# Timer555.net
KiCad netlist of a schematic drawn in Altium Designer
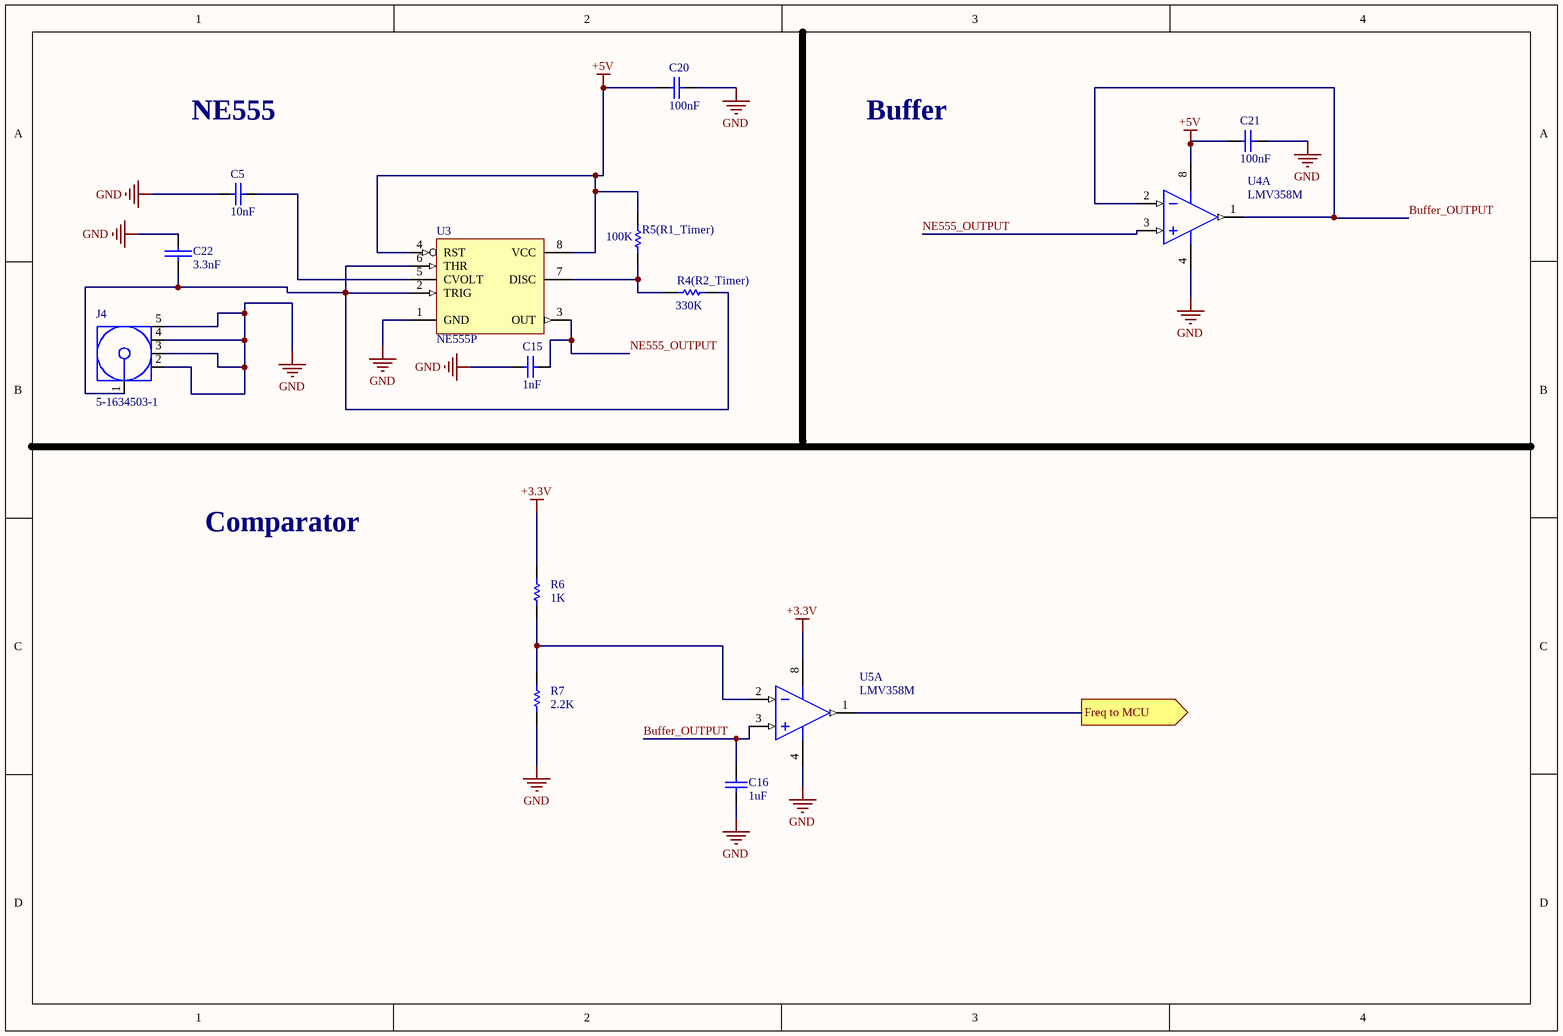
[diagram p0: Timer555.SchDoc]

(export (version "E")
  (design (tool "Eeschema 10.0.6"))
  (components
    (comp (ref "C5")
      (value "10nF")
      (footprint "CAPC2012N (0805)")
      (description "Bipolar Capacitor")
      (fields
        (field (name "VOLTAGE") "100V")
        (field (name "DESIGNER") "Eng. Saeid Jorablo")
        (field (name "PUBLISHER") "SJ Unlimited")
      )
      (libsource (lib "Passive Components") (part "CAP_Bipolar"))
    )
    (comp (ref "C15")
      (value "1nF")
      (footprint "CAPC3216M (1206)")
      (description "Bipolar Capacitor")
      (fields
        (field (name "VOLTAGE") "100V")
        (field (name "DESIGNER") "Eng. Saeid Jorablo")
        (field (name "PUBLISHER") "SJ Unlimited")
      )
      (libsource (lib "Passive Components") (part "CAP_Bipolar"))
    )
    (comp (ref "C16")
      (value "1uF")
      (footprint "CAPC3216M (1206)")
      (description "Bipolar Capacitor")
      (fields
        (field (name "VOLTAGE") "100V")
        (field (name "DESIGNER") "Eng. Saeid Jorablo")
        (field (name "PUBLISHER") "SJ Unlimited")
      )
      (libsource (lib "Passive Components") (part "CAP_Bipolar"))
    )
    (comp (ref "C20")
      (value "100nF")
      (footprint "CAPC2012N (0805)")
      (description "Bipolar Capacitor")
      (fields
        (field (name "VOLTAGE") "100V")
        (field (name "DESIGNER") "Eng. Saeid Jorablo")
        (field (name "PUBLISHER") "SJ Unlimited")
      )
      (libsource (lib "Passive Components") (part "CAP_Bipolar"))
    )
    (comp (ref "C21")
      (value "100nF")
      (footprint "CAPC2012N (0805)")
      (description "Bipolar Capacitor")
      (fields
        (field (name "VOLTAGE") "100V")
        (field (name "DESIGNER") "Eng. Saeid Jorablo")
        (field (name "PUBLISHER") "SJ Unlimited")
      )
      (libsource (lib "Passive Components") (part "CAP_Bipolar"))
    )
    (comp (ref "C22")
      (value "3.3nF")
      (footprint "Cap - 100nF")
      (description "Bipolar Capacitor")
      (fields (field (name "VOLTAGE") "100V") (field (name "DESIGNER") "Saeid Jorablo"))
      (libsource (lib "General 2") (part "Cap-Bipolar"))
    )
    (comp (ref "J4")
      (value "5-1634503-1")
      (footprint "TECO-5-1634503-1_V")
      (description "Female Header, Pitch 3.13 mm, Height 13.7 mm, Tail Length 4.5 mm, -55 to 85 degC, RoHS, Bulk")
      (fields (field (name "MANUFACTURER") "TE Connectivity"))
      (libsource (lib "Amir_Lib") (part "5-1634503-1"))
    )
    (comp (ref "R4(R2_Timer)")
      (value "330K")
      (footprint "Res-(1/2)")
      (description "Resistor")
      (fields
        (field (name "TOLERANCE") "5%")
        (field (name "POWER") "1/8 W")
        (field (name "DESIGNER") "Eng. Saeid Jorablo")
        (field (name "PUBLISHER") "SJ Unlimited")
      )
      (libsource (lib "Passive Components") (part "RES"))
    )
    (comp (ref "R5(R1_Timer)")
      (value "100K")
      (footprint "Res-(1/2)")
      (description "Resistor")
      (fields
        (field (name "TOLERANCE") "5%")
        (field (name "POWER") "1/8 W")
        (field (name "DESIGNER") "Eng. Saeid Jorablo")
        (field (name "PUBLISHER") "SJ Unlimited")
      )
      (libsource (lib "Passive Components") (part "RES"))
    )
    (comp (ref "R6")
      (value "1K")
      (footprint "RESC3216X60L (1206)")
      (description "Resistor")
      (fields
        (field (name "TOLERANCE") "5%")
        (field (name "POWER") "1/8 W")
        (field (name "DESIGNER") "Eng. Saeid Jorablo")
        (field (name "PUBLISHER") "SJ Unlimited")
      )
      (libsource (lib "Passive Components") (part "RES"))
    )
    (comp (ref "R7")
      (value "2.2K")
      (footprint "RESC3216X60L (1206)")
      (description "Resistor")
      (fields
        (field (name "TOLERANCE") "5%")
        (field (name "POWER") "1/8 W")
        (field (name "DESIGNER") "Eng. Saeid Jorablo")
        (field (name "PUBLISHER") "SJ Unlimited")
      )
      (libsource (lib "Passive Components") (part "RES"))
    )
    (comp (ref "U3")
      (value "NE555P")
      (footprint "P008")
      (description "Precision Timer")
      (fields (field (name "PUBLISHER") "Altium Limited"))
      (libsource (lib "TI Analog Timer Circuit") (part "NE555P"))
    )
    (comp (ref "U4")
      (value "LMV358M")
      (footprint "M08A_M")
      (description "General Purpose, Low Voltage, Rail-to-Rail Output Operational Amplifiers, 8-pin Narrow SOIC")
      (fields (field (name "MANUFACTURER") "National Semiconductor"))
      (libsource (lib "Xilinx") (part "LMV358M"))
    )
    (comp (ref "U5")
      (value "LMV358M")
      (footprint "M08A_M")
      (description "General Purpose, Low Voltage, Rail-to-Rail Output Operational Amplifiers, 8-pin Narrow SOIC")
      (fields (field (name "MANUFACTURER") "National Semiconductor"))
      (libsource (lib "Xilinx") (part "LMV358M"))
    )
  )
  (nets
    (net (code "1") (name "+3.3V") (class "Default")
      (node (ref "R6") (pin "2") (pinfunction "2_2") (pintype "passive"))
      (node (ref "U5") (pin "8") (pinfunction "V+_8") (pintype "power_in"))
    )
    (net (code "2") (name "+5V") (class "Default")
      (node (ref "C20") (pin "1") (pinfunction "+_1") (pintype "passive"))
      (node (ref "C21") (pin "1") (pinfunction "+_1") (pintype "passive"))
      (node (ref "R5(R1_Timer)") (pin "2") (pinfunction "2_2") (pintype "passive"))
      (node (ref "U3") (pin "4") (pinfunction "RST_4") (pintype "input"))
      (node (ref "U3") (pin "8") (pinfunction "VCC_8") (pintype "power_in"))
      (node (ref "U4") (pin "8") (pinfunction "V+_8") (pintype "power_in"))
    )
    (net (code "3") (name "/Buffer_OUTPUT") (class "Default")
      (node (ref "C16") (pin "1") (pinfunction "+_1") (pintype "passive"))
      (node (ref "U4") (pin "1") (pinfunction "OUTA_1") (pintype "output"))
      (node (ref "U4") (pin "2") (pinfunction "INA-_2") (pintype "input"))
      (node (ref "U5") (pin "3") (pinfunction "INA+_3") (pintype "input"))
    )
    (net (code "4") (name "/Freq to MCU") (class "Default")
      (node (ref "U5") (pin "1") (pinfunction "OUTA_1") (pintype "output"))
    )
    (net (code "5") (name "/NE555_OUTPUT") (class "Default")
      (node (ref "C15") (pin "2") (pinfunction "-_2") (pintype "passive"))
      (node (ref "U3") (pin "3") (pinfunction "OUT_3") (pintype "output"))
      (node (ref "U4") (pin "3") (pinfunction "INA+_3") (pintype "input"))
    )
    (net (code "6") (name "GND") (class "Default")
      (node (ref "C15") (pin "1") (pinfunction "+_1") (pintype "passive"))
      (node (ref "C16") (pin "2") (pinfunction "-_2") (pintype "passive"))
      (node (ref "C20") (pin "2") (pinfunction "-_2") (pintype "passive"))
      (node (ref "C21") (pin "2") (pinfunction "-_2") (pintype "passive"))
      (node (ref "C22") (pin "1") (pinfunction "+_1") (pintype "passive"))
      (node (ref "C5") (pin "1") (pinfunction "+_1") (pintype "passive"))
      (node (ref "J4") (pin "2") (pinfunction "2_2") (pintype "passive"))
      (node (ref "J4") (pin "3") (pinfunction "3_3") (pintype "passive"))
      (node (ref "J4") (pin "4") (pinfunction "4_4") (pintype "passive"))
      (node (ref "J4") (pin "5") (pinfunction "5_5") (pintype "passive"))
      (node (ref "R7") (pin "1") (pinfunction "1_1") (pintype "passive"))
      (node (ref "U3") (pin "1") (pinfunction "GND_1") (pintype "power_in"))
      (node (ref "U4") (pin "4") (pinfunction "V-_4") (pintype "power_in"))
      (node (ref "U5") (pin "4") (pinfunction "V-_4") (pintype "power_in"))
    )
    (net (code "7") (name "Net-(C5--)") (class "Default")
      (node (ref "C5") (pin "2") (pinfunction "-_2") (pintype "passive"))
      (node (ref "U3") (pin "5") (pinfunction "CVOLT_5") (pintype "passive"))
    )
    (net (code "8") (name "Net-(C22--)") (class "Default")
      (node (ref "C22") (pin "2") (pinfunction "-_2") (pintype "passive"))
      (node (ref "J4") (pin "1") (pinfunction "1_1") (pintype "passive"))
      (node (ref "R4(R2_Timer)") (pin "2") (pinfunction "2_2") (pintype "passive"))
      (node (ref "U3") (pin "2") (pinfunction "TRIG_2") (pintype "input"))
      (node (ref "U3") (pin "6") (pinfunction "THR_6") (pintype "input"))
    )
    (net (code "9") (name "Net-(U3-DISC)") (class "Default")
      (node (ref "R4(R2_Timer)") (pin "1") (pinfunction "1_1") (pintype "passive"))
      (node (ref "R5(R1_Timer)") (pin "1") (pinfunction "1_1") (pintype "passive"))
      (node (ref "U3") (pin "7") (pinfunction "DISC_7") (pintype "open_collector"))
    )
    (net (code "10") (name "Net-(U5A-INA-)") (class "Default")
      (node (ref "R6") (pin "1") (pinfunction "1_1") (pintype "passive"))
      (node (ref "R7") (pin "2") (pinfunction "2_2") (pintype "passive"))
      (node (ref "U5") (pin "2") (pinfunction "INA-_2") (pintype "input"))
    )
  )
)
